# CheerLightsv2.net
KiCad netlist of a schematic drawn in EAGLE
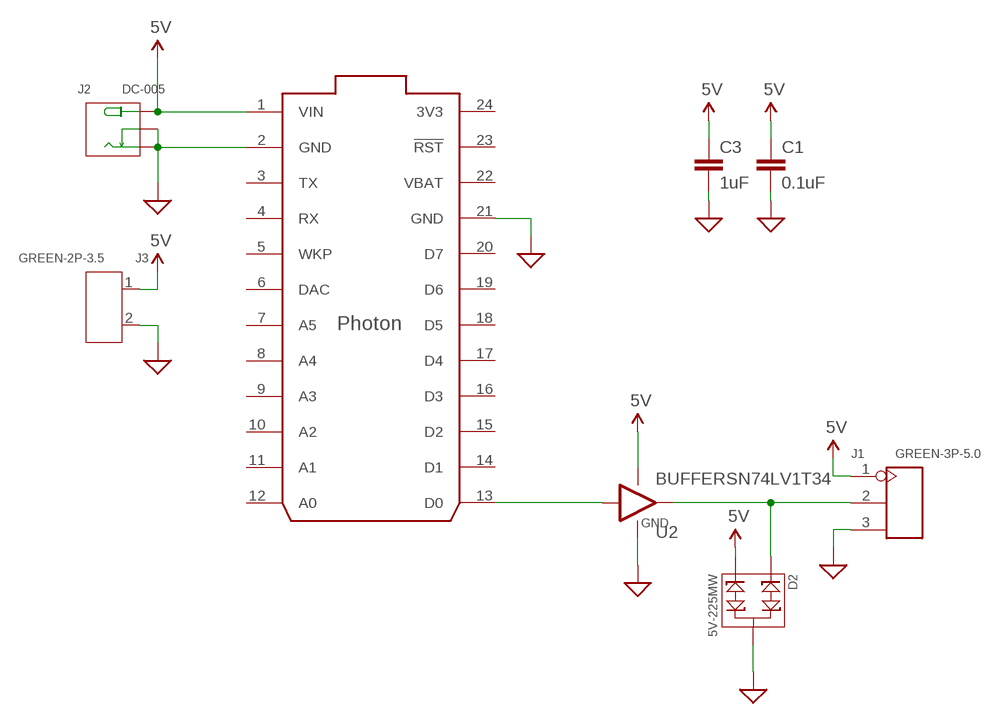
[diagram p0: schematic, sheet 1]

(export (version "E")
  (design (tool "Eeschema 10.0.6"))
  (components
    (comp (ref "C1")
      (value "0.1uF")
      (footprint "eagle-import:0805")
      (libsource (lib "eagle-import") (part "CAP0805"))
    )
    (comp (ref "C3")
      (value "1uF")
      (footprint "eagle-import:0805")
      (libsource (lib "eagle-import") (part "CAP0805"))
    )
    (comp (ref "D2")
      (value "5V-225MW")
      (footprint "eagle-import:SOT-23")
      (fields (field (name "MPN") "CESD5V0AP") (field (name "PARTNO") "TPD2E009DBZR"))
      (libsource (lib "eagle-import") (part "SMD-DIODE-TVS-5V-225MW(SOT-23)"))
    )
    (comp (ref "J1")
      (value "GREEN-3P-5.0")
      (footprint "eagle-import:H3-5.0-15.5X8.0MM")
      (fields (field (name "PARTNO") "1935174"))
      (libsource (lib "eagle-import") (part "SCREW-TERMINAL-GREEN(3P-5.0)"))
    )
    (comp (ref "J2")
      (value "DC-005")
      (footprint "eagle-import:DCJ3P-14.2X11.0X9.0MM")
      (fields (field (name "PARTNO") "EJ508A"))
      (libsource (lib "eagle-import") (part "CONN-POWER-JACK-2.1MM(DC-005)"))
    )
    (comp (ref "J3")
      (value "GREEN-2P-3.5")
      (footprint "eagle-import:H2-3.5-7.0X7.0MM")
      (libsource (lib "eagle-import") (part "SCREW-TERMINAL-GREEN(2P-3.5)"))
    )
    (comp (ref "U1")
      (value "PHOTON_WITH_HEADERS")
      (footprint "eagle-import:PHOTON")
      (libsource (lib "eagle-import") (part "PHOTON_WITH_HEADERS"))
    )
    (comp (ref "U2")
      (value "BUFFERSN74LV1T34")
      (footprint "eagle-import:SOT23-5")
      (libsource (lib "eagle-import") (part "BUFFERSN74LV1T34"))
    )
  )
  (nets
    (net (code "1") (name "/3V3") (class "Default")
      (node (ref "U1") (pin "24") (pinfunction "3V3_24") (pintype "power_in"))
    )
    (net (code "2") (name "/VBAT") (class "Default")
      (node (ref "U1") (pin "22") (pinfunction "VBAT_22") (pintype "power_in"))
    )
    (net (code "3") (name "5V") (class "Default")
      (node (ref "C1") (pin "1") (pinfunction "1_1") (pintype "passive"))
      (node (ref "C3") (pin "1") (pinfunction "1_1") (pintype "passive"))
      (node (ref "D2") (pin "2") (pinfunction "2_2") (pintype "power_in"))
      (node (ref "J1") (pin "1") (pinfunction "P$1_1") (pintype "bidirectional"))
      (node (ref "J2") (pin "+") (pinfunction "+_+") (pintype "bidirectional"))
      (node (ref "J3") (pin "1") (pinfunction "1_1") (pintype "bidirectional"))
      (node (ref "U1") (pin "1") (pinfunction "VIN_1") (pintype "power_in"))
      (node (ref "U2") (pin "5") (pinfunction "PWR_5") (pintype "power_in"))
    )
    (net (code "4") (name "GND") (class "Default")
      (node (ref "C1") (pin "2") (pinfunction "2_2") (pintype "passive"))
      (node (ref "C3") (pin "2") (pinfunction "2_2") (pintype "passive"))
      (node (ref "D2") (pin "3") (pinfunction "3_3") (pintype "bidirectional"))
      (node (ref "J1") (pin "3") (pinfunction "P$3_3") (pintype "bidirectional"))
      (node (ref "J2") (pin "-1") (pinfunction "-_-1") (pintype "bidirectional"))
      (node (ref "J2") (pin "-2") (pinfunction "CDN_-2") (pintype "bidirectional"))
      (node (ref "J3") (pin "2") (pinfunction "2_2") (pintype "bidirectional"))
      (node (ref "U1") (pin "2") (pinfunction "GND_2") (pintype "power_in"))
      (node (ref "U1") (pin "21") (pinfunction "GND_21") (pintype "power_in"))
      (node (ref "U2") (pin "3") (pinfunction "GND_3") (pintype "power_in"))
    )
    (net (code "5") (name "Net-(J1-P$2)") (class "Default")
      (node (ref "D2") (pin "1") (pinfunction "1_1") (pintype "power_in"))
      (node (ref "J1") (pin "2") (pinfunction "P$2_2") (pintype "bidirectional"))
      (node (ref "U2") (pin "4") (pinfunction "OUT_4") (pintype "output"))
    )
    (net (code "6") (name "Net-(U1-D0)") (class "Default")
      (node (ref "U1") (pin "13") (pinfunction "D0_13") (pintype "bidirectional"))
      (node (ref "U2") (pin "2") (pinfunction "IN_2") (pintype "input"))
    )
    (net (code "7") (name "unconnected-(U1-A0-Pad12)") (class "Default")
      (node (ref "U1") (pin "12") (pinfunction "A0_12") (pintype "bidirectional"))
    )
    (net (code "8") (name "unconnected-(U1-A1-Pad11)") (class "Default")
      (node (ref "U1") (pin "11") (pinfunction "A1_11") (pintype "bidirectional"))
    )
    (net (code "9") (name "unconnected-(U1-A2-Pad10)") (class "Default")
      (node (ref "U1") (pin "10") (pinfunction "A2_10") (pintype "bidirectional"))
    )
    (net (code "10") (name "unconnected-(U1-A3-Pad9)") (class "Default")
      (node (ref "U1") (pin "9") (pinfunction "A3_9") (pintype "bidirectional"))
    )
    (net (code "11") (name "unconnected-(U1-A4-Pad8)") (class "Default")
      (node (ref "U1") (pin "8") (pinfunction "A4_8") (pintype "bidirectional"))
    )
    (net (code "12") (name "unconnected-(U1-A5-Pad7)") (class "Default")
      (node (ref "U1") (pin "7") (pinfunction "A5_7") (pintype "bidirectional"))
    )
    (net (code "13") (name "unconnected-(U1-D1-Pad14)") (class "Default")
      (node (ref "U1") (pin "14") (pinfunction "D1_14") (pintype "bidirectional"))
    )
    (net (code "14") (name "unconnected-(U1-D2-Pad15)") (class "Default")
      (node (ref "U1") (pin "15") (pinfunction "D2_15") (pintype "bidirectional"))
    )
    (net (code "15") (name "unconnected-(U1-D3-Pad16)") (class "Default")
      (node (ref "U1") (pin "16") (pinfunction "D3_16") (pintype "bidirectional"))
    )
    (net (code "16") (name "unconnected-(U1-D4-Pad17)") (class "Default")
      (node (ref "U1") (pin "17") (pinfunction "D4_17") (pintype "bidirectional"))
    )
    (net (code "17") (name "unconnected-(U1-D5-Pad18)") (class "Default")
      (node (ref "U1") (pin "18") (pinfunction "D5_18") (pintype "bidirectional"))
    )
    (net (code "18") (name "unconnected-(U1-D6-Pad19)") (class "Default")
      (node (ref "U1") (pin "19") (pinfunction "D6_19") (pintype "bidirectional"))
    )
    (net (code "19") (name "unconnected-(U1-D7-Pad20)") (class "Default")
      (node (ref "U1") (pin "20") (pinfunction "D7_20") (pintype "bidirectional"))
    )
    (net (code "20") (name "unconnected-(U1-DAC-Pad6)") (class "Default")
      (node (ref "U1") (pin "6") (pinfunction "DAC_6") (pintype "bidirectional"))
    )
    (net (code "21") (name "unconnected-(U1-RX-Pad4)") (class "Default")
      (node (ref "U1") (pin "4") (pinfunction "RX_4") (pintype "bidirectional"))
    )
    (net (code "22") (name "unconnected-(U1-TX-Pad3)") (class "Default")
      (node (ref "U1") (pin "3") (pinfunction "TX_3") (pintype "bidirectional"))
    )
    (net (code "23") (name "unconnected-(U1-WKP-Pad5)") (class "Default")
      (node (ref "U1") (pin "5") (pinfunction "WKP_5") (pintype "bidirectional"))
    )
    (net (code "24") (name "unconnected-(U1-~{RST}-Pad23)") (class "Default")
      (node (ref "U1") (pin "23") (pinfunction "~{RST}_23") (pintype "bidirectional"))
    )
  )
)
